# w32_dmx512_Schematic.net
KiCad netlist of a schematic drawn in Altium Designer
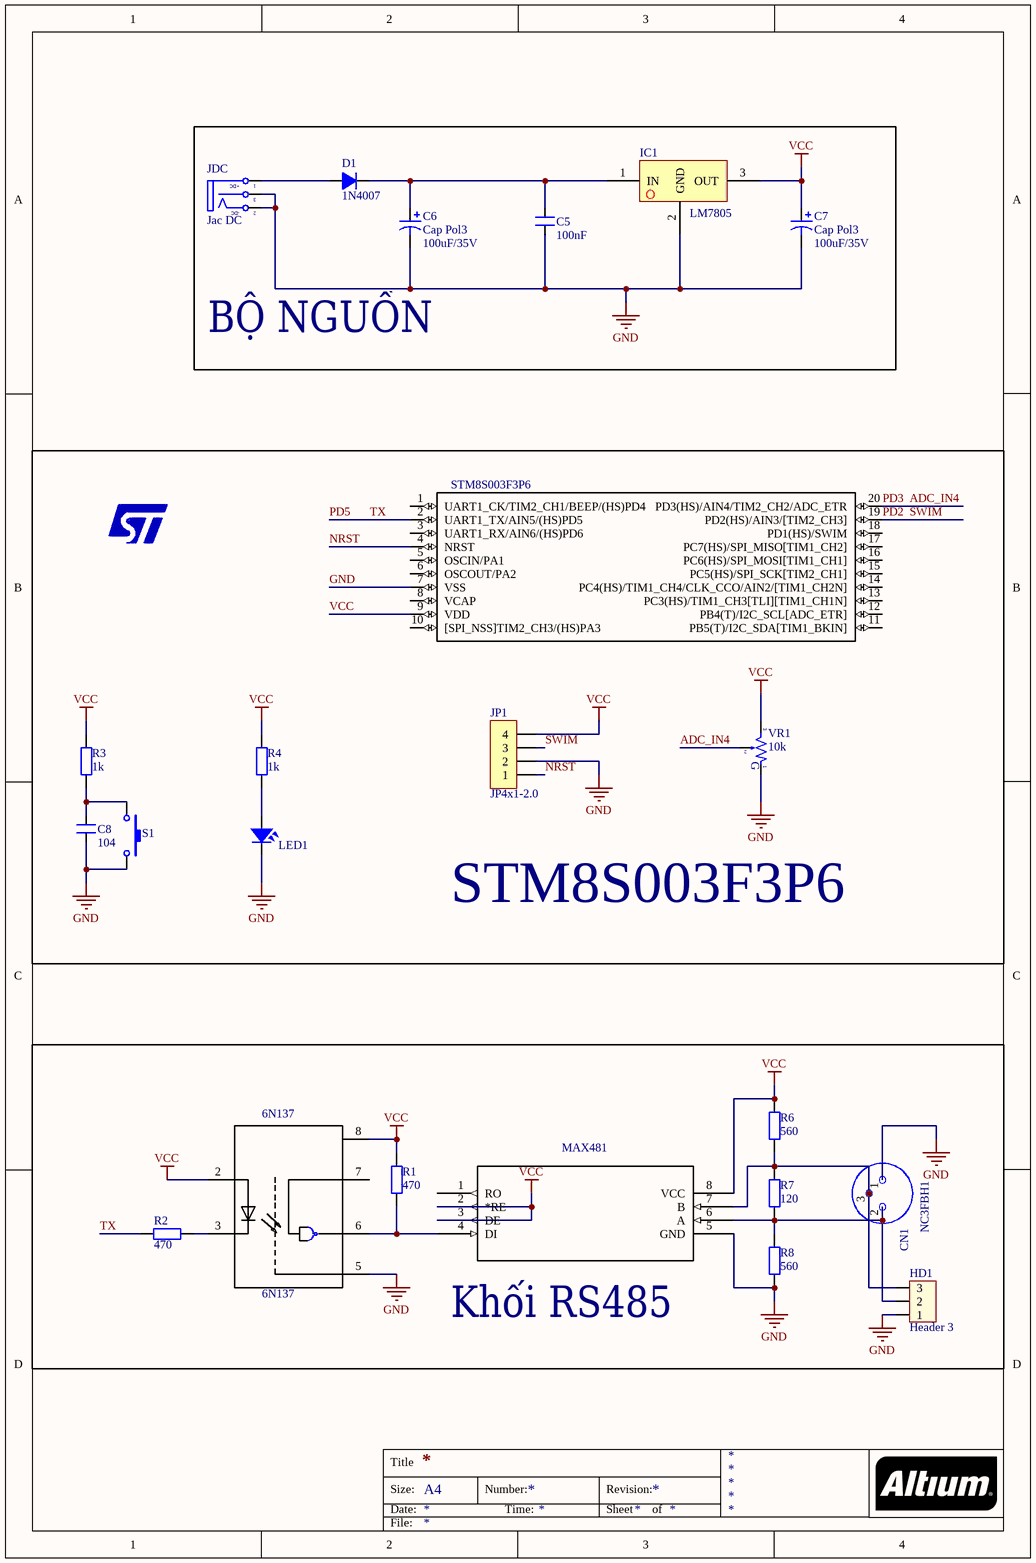
[diagram p0: w32_dmx512_Schematic.SchDoc]

(export (version "E")
  (design (tool "Eeschema 10.0.6"))
  (components
    (comp (ref "6N137")
      (value "6N137")
      (footprint "DIP762W50P254L977H451Q8")
      (description "High CMR, High Speed TTL Compatible Optocouplers")
      (fields (field (name "MF") "Vishay Semiconductor"))
      (libsource (lib "6N137") (part "6N137"))
    )
    (comp (ref "C5")
      (value "100nF")
      (footprint "CN150")
      (description "Capacitor Ceramic")
      (fields (field (name "Comment") "104"))
      (libsource (lib "SRC") (part "CN1.5"))
    )
    (comp (ref "C6")
      (value "Cap Pol3")
      (footprint "CP2/5")
      (description "Polarized Capacitor (Surface Mount)")
      (fields (field (name "ALTIUM_VALUE") "100uF/35V") (field (name "PUBLISHER") "Altium Limited"))
      (libsource (lib "syhaunguyen") (part "Cap Pol3"))
    )
    (comp (ref "C7")
      (value "Cap Pol3")
      (footprint "CP2/5")
      (description "Polarized Capacitor (Surface Mount)")
      (fields (field (name "ALTIUM_VALUE") "100uF/35V") (field (name "PUBLISHER") "Altium Limited"))
      (libsource (lib "syhaunguyen") (part "Cap Pol3"))
    )
    (comp (ref "C8")
      (value "104")
      (footprint "CN150")
      (description "Capacitor Ceramic")
      (libsource (lib "SRC") (part "CN1.5"))
    )
    (comp (ref "CN1")
      (value "NC3FBH1")
      (footprint "NC3FBH1")
      (description "XLR Receptacle; Female; Gold; Horizontal PCB Mount; 0.996 in.; Ground")
      (fields (field (name "MF") "Neutrik"))
      (libsource (lib "NC3FBH1") (part "NC3FBH1"))
    )
    (comp (ref "D1")
      (value "1N4007")
      (footprint "D2A")
      (description "Diode 1A")
      (libsource (lib "syhaunguyen") (part "D1A"))
    )
    (comp (ref "HD1")
      (value "Header 3")
      (footprint "HED3")
      (description "Header 3 (Green)")
      (libsource (lib "takahashi") (part "Hed3"))
    )
    (comp (ref "IC1") (value "LM7805") (footprint "7805:7805") (libsource (lib "7805") (part "LM7805")))
    (comp (ref "JDC")
      (value "Jac DC")
      (footprint "DC-IN")
      (description "Jac DC input")
      (libsource (lib "syhaunguyen") (part "DCIN"))
    )
    (comp (ref "JP1")
      (value "JP4x1-2.0")
      (footprint "J4-D1T")
      (description "WR-PHD 2.00 mm Socket Header")
      (fields
        (field (name "MANUFACTURER") "Würth Elektronik eiSos GmbH")
        (field (name "PARTNO") "62000411821")
        (field (name "CREATED BY") "Karrer Zheng")
      )
      (libsource (lib "LIBRARY") (part "JP4x1-2.0"))
    )
    (comp (ref "LED1") (value "LED") (footprint "LED-RED-0805") (libsource (lib "LIBRARY") (part "LED SMD")))
    (comp (ref "M1")
      (value "STLOGO")
      (footprint "STLOGO-SILVER")
      (libsource (lib "vh_altium_library") (part "STLOGO"))
    )
    (comp (ref "MAX481")
      (value "MAX481CPA")
      (footprint "21-0043D_8")
      (description "Single Transmitter/Receiver RS-422/RS-485 8-Pin PDIP N")
      (fields (field (name "MF") "Maxim Integrated"))
      (libsource (lib "MAX481CPA") (part "MAX481CPA"))
    )
    (comp (ref "R1")
      (value "470")
      (footprint "DIEN TRO 1/4 W")
      (description "Resistor")
      (fields (field (name "Comment") "R0.4W") (field (name "PUBLISHER") "Altium Limited"))
      (libsource (lib "") (part "Res 1/4 W_2"))
    )
    (comp (ref "R2")
      (value "470")
      (footprint "DIEN TRO 1/4 W")
      (description "Resistor")
      (fields (field (name "Comment") "R0.4W") (field (name "PUBLISHER") "Altium Limited"))
      (libsource (lib "NBBLib-14-03-2012") (part "Res 1/4 W"))
    )
    (comp (ref "R3")
      (value "1k")
      (footprint "DIEN TRO 1/4 W")
      (description "Resistor")
      (fields (field (name "Comment") "R0.4W") (field (name "PUBLISHER") "Altium Limited"))
      (libsource (lib "") (part "Res 1/4 W_1"))
    )
    (comp (ref "R4")
      (value "1k")
      (footprint "DIEN TRO 1/4 W")
      (description "Resistor")
      (fields (field (name "Comment") "R0.4W") (field (name "PUBLISHER") "Altium Limited"))
      (libsource (lib "") (part "Res 1/4 W_1"))
    )
    (comp (ref "R6")
      (value "560")
      (footprint "DIEN TRO 1/4 W")
      (description "Resistor")
      (fields (field (name "Comment") "R0.4W") (field (name "PUBLISHER") "Altium Limited"))
      (libsource (lib "") (part "Res 1/4 W_1"))
    )
    (comp (ref "R7")
      (value "120")
      (footprint "DIEN TRO 1/4 W")
      (description "Resistor")
      (fields (field (name "Comment") "R0.4W") (field (name "PUBLISHER") "Altium Limited"))
      (libsource (lib "") (part "Res 1/4 W_1"))
    )
    (comp (ref "R8")
      (value "560")
      (footprint "DIEN TRO 1/4 W")
      (description "Resistor")
      (fields (field (name "Comment") "R0.4W") (field (name "PUBLISHER") "Altium Limited"))
      (libsource (lib "") (part "Res 1/4 W_1"))
    )
    (comp (ref "S1")
      (value "SW-SMD")
      (footprint "SW-SMD")
      (description "Switch")
      (fields (field (name "PUBLISHER") "Altium Limited"))
      (libsource (lib "NBBLib-14-03-2012") (part "SW-SMD"))
    )
    (comp (ref "STM8S003F3P6")
      (value "STM8S003F3P6")
      (footprint "STM8S003F3P6:TSSOP20")
      (description "Mainstream Value line 8-bit MCU with 8 Kbytes Flash, 16 MHz CPU, integrated EEPROM")
      (fields (field (name "MF") "STMicroelectronics"))
      (libsource (lib "STM8S003F3P6") (part "STM8S003F3P6"))
    )
    (comp (ref "VR1")
      (value "10k")
      (footprint "VR-S1")
      (description "Var Resistor")
      (libsource (lib "LIBRARY") (part "VR-S"))
    )
  )
  (nets
    (net (code "1") (name "/ADC_IN4") (class "Default")
      (node (ref "STM8S003F3P6") (pin "20") (pinfunction "PD3(HS)/AIN4/TIM2_CH2/ADC_ETR_20") (pintype "bidirectional"))
      (node (ref "VR1") (pin "2") (pinfunction "2_2") (pintype "passive"))
    )
    (net (code "2") (name "/NRST") (class "Default")
      (node (ref "JP1") (pin "1") (pinfunction "1_1") (pintype "passive"))
      (node (ref "STM8S003F3P6") (pin "4") (pinfunction "NRST_4") (pintype "bidirectional"))
    )
    (net (code "3") (name "/PD2") (class "Default")
      (node (ref "JP1") (pin "3") (pinfunction "3_3") (pintype "passive"))
      (node (ref "STM8S003F3P6") (pin "19") (pinfunction "PD2(HS)/AIN3/[TIM2_CH3]_19") (pintype "bidirectional"))
    )
    (net (code "4") (name "/PD5") (class "Default")
      (node (ref "R2") (pin "1") (pinfunction "1_1") (pintype "passive"))
      (node (ref "STM8S003F3P6") (pin "2") (pinfunction "UART1_TX/AIN5/(HS)PD5_2") (pintype "bidirectional"))
    )
    (net (code "5") (name "GND") (class "Default")
      (node (ref "6N137") (pin "5") (pinfunction "GND_5") (pintype "power_in"))
      (node (ref "C5") (pin "1") (pinfunction "1_1") (pintype "passive"))
      (node (ref "C6") (pin "2") (pinfunction "2_2") (pintype "passive"))
      (node (ref "C7") (pin "2") (pinfunction "2_2") (pintype "passive"))
      (node (ref "C8") (pin "2") (pinfunction "2_2") (pintype "passive"))
      (node (ref "CN1") (pin "1") (pinfunction "1_1") (pintype "passive"))
      (node (ref "HD1") (pin "1") (pinfunction "1_1") (pintype "passive"))
      (node (ref "IC1") (pin "2") (pinfunction "GND_2") (pintype "passive"))
      (node (ref "JDC") (pin "2") (pinfunction "TN_2") (pintype "passive"))
      (node (ref "JDC") (pin "3") (pinfunction "S_3") (pintype "power_in"))
      (node (ref "JP1") (pin "2") (pinfunction "2_2") (pintype "passive"))
      (node (ref "LED1") (pin "2") (pinfunction "2_2") (pintype "passive"))
      (node (ref "MAX481") (pin "5") (pinfunction "GND_5") (pintype "power_in"))
      (node (ref "R8") (pin "1") (pinfunction "1_1") (pintype "passive"))
      (node (ref "S1") (pin "2") (pinfunction "2_2") (pintype "passive"))
      (node (ref "STM8S003F3P6") (pin "7") (pinfunction "VSS_7") (pintype "bidirectional"))
      (node (ref "VR1") (pin "1") (pinfunction "1_1") (pintype "passive"))
    )
    (net (code "6") (name "Net-(6N137-C)") (class "Default")
      (node (ref "6N137") (pin "3") (pinfunction "C_3") (pintype "passive"))
      (node (ref "R2") (pin "2") (pinfunction "2_2") (pintype "passive"))
    )
    (net (code "7") (name "Net-(6N137-VO)") (class "Default")
      (node (ref "6N137") (pin "6") (pinfunction "VO_6") (pintype "passive"))
      (node (ref "MAX481") (pin "4") (pinfunction "DI_4") (pintype "input"))
      (node (ref "R1") (pin "2") (pinfunction "2_2") (pintype "passive"))
    )
    (net (code "8") (name "Net-(C8-Pad1)") (class "Default")
      (node (ref "C8") (pin "1") (pinfunction "1_1") (pintype "passive"))
      (node (ref "R3") (pin "1") (pinfunction "1_1") (pintype "passive"))
      (node (ref "S1") (pin "1") (pinfunction "1_1") (pintype "passive"))
    )
    (net (code "9") (name "Net-(D1-A)") (class "Default")
      (node (ref "D1") (pin "1") (pinfunction "A_1") (pintype "passive"))
      (node (ref "JDC") (pin "1") (pinfunction "T_1") (pintype "passive"))
    )
    (net (code "10") (name "Net-(D1-K)") (class "Default")
      (node (ref "C5") (pin "2") (pinfunction "2_2") (pintype "passive"))
      (node (ref "C6") (pin "1") (pinfunction "1_1") (pintype "passive"))
      (node (ref "D1") (pin "2") (pinfunction "K_2") (pintype "passive"))
      (node (ref "IC1") (pin "1") (pinfunction "IN_1") (pintype "passive"))
    )
    (net (code "11") (name "Net-(LED1-Pad1)") (class "Default")
      (node (ref "LED1") (pin "1") (pinfunction "1_1") (pintype "passive"))
      (node (ref "R4") (pin "1") (pinfunction "1_1") (pintype "passive"))
    )
    (net (code "12") (name "Net-(MAX481-A)") (class "Default")
      (node (ref "CN1") (pin "2") (pinfunction "2_2") (pintype "passive"))
      (node (ref "HD1") (pin "2") (pinfunction "2_2") (pintype "passive"))
      (node (ref "MAX481") (pin "6") (pinfunction "A_6") (pintype "input"))
      (node (ref "R7") (pin "1") (pinfunction "1_1") (pintype "passive"))
      (node (ref "R8") (pin "2") (pinfunction "2_2") (pintype "passive"))
    )
    (net (code "13") (name "Net-(MAX481-B)") (class "Default")
      (node (ref "CN1") (pin "3") (pinfunction "3_3") (pintype "passive"))
      (node (ref "HD1") (pin "3") (pinfunction "3_3") (pintype "passive"))
      (node (ref "MAX481") (pin "7") (pinfunction "B_7") (pintype "input"))
      (node (ref "R6") (pin "1") (pinfunction "1_1") (pintype "passive"))
      (node (ref "R7") (pin "2") (pinfunction "2_2") (pintype "passive"))
    )
    (net (code "14") (name "VCC") (class "Default")
      (node (ref "6N137") (pin "2") (pinfunction "A_2") (pintype "passive"))
      (node (ref "6N137") (pin "8") (pinfunction "VCC_8") (pintype "power_in"))
      (node (ref "C7") (pin "1") (pinfunction "1_1") (pintype "passive"))
      (node (ref "IC1") (pin "3") (pinfunction "OUT_3") (pintype "passive"))
      (node (ref "JP1") (pin "4") (pinfunction "4_4") (pintype "passive"))
      (node (ref "MAX481") (pin "2") (pinfunction "*RE_2") (pintype "output"))
      (node (ref "MAX481") (pin "3") (pinfunction "DE_3") (pintype "output"))
      (node (ref "MAX481") (pin "8") (pinfunction "VCC_8") (pintype "power_in"))
      (node (ref "R1") (pin "1") (pinfunction "1_1") (pintype "passive"))
      (node (ref "R3") (pin "2") (pinfunction "2_2") (pintype "passive"))
      (node (ref "R4") (pin "2") (pinfunction "2_2") (pintype "passive"))
      (node (ref "R6") (pin "2") (pinfunction "2_2") (pintype "passive"))
      (node (ref "STM8S003F3P6") (pin "9") (pinfunction "VDD_9") (pintype "bidirectional"))
      (node (ref "VR1") (pin "3") (pinfunction "3_3") (pintype "passive"))
    )
    (net (code "15") (name "unconnected-(6N137-VE-Pad7)") (class "Default")
      (node (ref "6N137") (pin "7") (pinfunction "VE_7") (pintype "passive"))
    )
    (net (code "16") (name "unconnected-(MAX481-RO-Pad1)") (class "Default")
      (node (ref "MAX481") (pin "1") (pinfunction "RO_1") (pintype "output"))
    )
    (net (code "17") (name "unconnected-(STM8S003F3P6-OSCIN{slash}PA1-Pad5)") (class "Default")
      (node (ref "STM8S003F3P6") (pin "5") (pinfunction "OSCIN/PA1_5") (pintype "bidirectional"))
    )
    (net (code "18") (name "unconnected-(STM8S003F3P6-OSCOUT{slash}PA2-Pad6)") (class "Default")
      (node (ref "STM8S003F3P6") (pin "6") (pinfunction "OSCOUT/PA2_6") (pintype "bidirectional"))
    )
    (net (code "19") (name "unconnected-(STM8S003F3P6-PB4(T){slash}I2C_SCL[ADC_ETR]-Pad12)") (class "Default")
      (node (ref "STM8S003F3P6") (pin "12") (pinfunction "PB4(T)/I2C_SCL[ADC_ETR]_12") (pintype "bidirectional"))
    )
    (net (code "20") (name "unconnected-(STM8S003F3P6-PB5(T){slash}I2C_SDA[TIM1_BKIN]-Pad11)") (class "Default")
      (node (ref "STM8S003F3P6") (pin "11") (pinfunction "PB5(T)/I2C_SDA[TIM1_BKIN]_11") (pintype "bidirectional"))
    )
    (net (code "21") (name "unconnected-(STM8S003F3P6-PC3(HS){slash}TIM1_CH3[TLI][TIM1_CH1N]-Pad13)") (class "Default")
      (node (ref "STM8S003F3P6") (pin "13") (pinfunction "PC3(HS)/TIM1_CH3[TLI][TIM1_CH1N]_13") (pintype "bidirectional"))
    )
    (net (code "22") (name "unconnected-(STM8S003F3P6-PC4(HS){slash}TIM1_CH4{slash}CLK_CCO{slash}AIN2{slash}[TIM1_CH2N]-Pad14)") (class "Default")
      (node (ref "STM8S003F3P6") (pin "14") (pinfunction "PC4(HS)/TIM1_CH4/CLK_CCO/AIN2/[TIM1_CH2N]_14") (pintype "bidirectional"))
    )
    (net (code "23") (name "unconnected-(STM8S003F3P6-PC5(HS){slash}SPI_SCK[TIM2_CH1]-Pad15)") (class "Default")
      (node (ref "STM8S003F3P6") (pin "15") (pinfunction "PC5(HS)/SPI_SCK[TIM2_CH1]_15") (pintype "bidirectional"))
    )
    (net (code "24") (name "unconnected-(STM8S003F3P6-PC6(HS){slash}SPI_MOSI[TIM1_CH1]-Pad16)") (class "Default")
      (node (ref "STM8S003F3P6") (pin "16") (pinfunction "PC6(HS)/SPI_MOSI[TIM1_CH1]_16") (pintype "bidirectional"))
    )
    (net (code "25") (name "unconnected-(STM8S003F3P6-PC7(HS){slash}SPI_MISO[TIM1_CH2]-Pad17)") (class "Default")
      (node (ref "STM8S003F3P6") (pin "17") (pinfunction "PC7(HS)/SPI_MISO[TIM1_CH2]_17") (pintype "bidirectional"))
    )
    (net (code "26") (name "unconnected-(STM8S003F3P6-PD1(HS){slash}SWIM-Pad18)") (class "Default")
      (node (ref "STM8S003F3P6") (pin "18") (pinfunction "PD1(HS)/SWIM_18") (pintype "bidirectional"))
    )
    (net (code "27") (name "unconnected-(STM8S003F3P6-UART1_CK{slash}TIM2_CH1{slash}BEEP{slash}(HS)PD4-Pad1)") (class "Default")
      (node (ref "STM8S003F3P6") (pin "1") (pinfunction "UART1_CK/TIM2_CH1/BEEP/(HS)PD4_1") (pintype "bidirectional"))
    )
    (net (code "28") (name "unconnected-(STM8S003F3P6-UART1_RX{slash}AIN6{slash}(HS)PD6-Pad3)") (class "Default")
      (node (ref "STM8S003F3P6") (pin "3") (pinfunction "UART1_RX/AIN6/(HS)PD6_3") (pintype "bidirectional"))
    )
    (net (code "29") (name "unconnected-(STM8S003F3P6-VCAP-Pad8)") (class "Default")
      (node (ref "STM8S003F3P6") (pin "8") (pinfunction "VCAP_8") (pintype "bidirectional"))
    )
    (net (code "30") (name "unconnected-(STM8S003F3P6-[SPI_NSS]TIM2_CH3{slash}(HS)PA3-Pad10)") (class "Default")
      (node (ref "STM8S003F3P6") (pin "10") (pinfunction "[SPI_NSS]TIM2_CH3/(HS)PA3_10") (pintype "bidirectional"))
    )
  )
)
